# Decoder_relay_4bit_REV_0.net
KiCad netlist of a schematic drawn in EAGLE
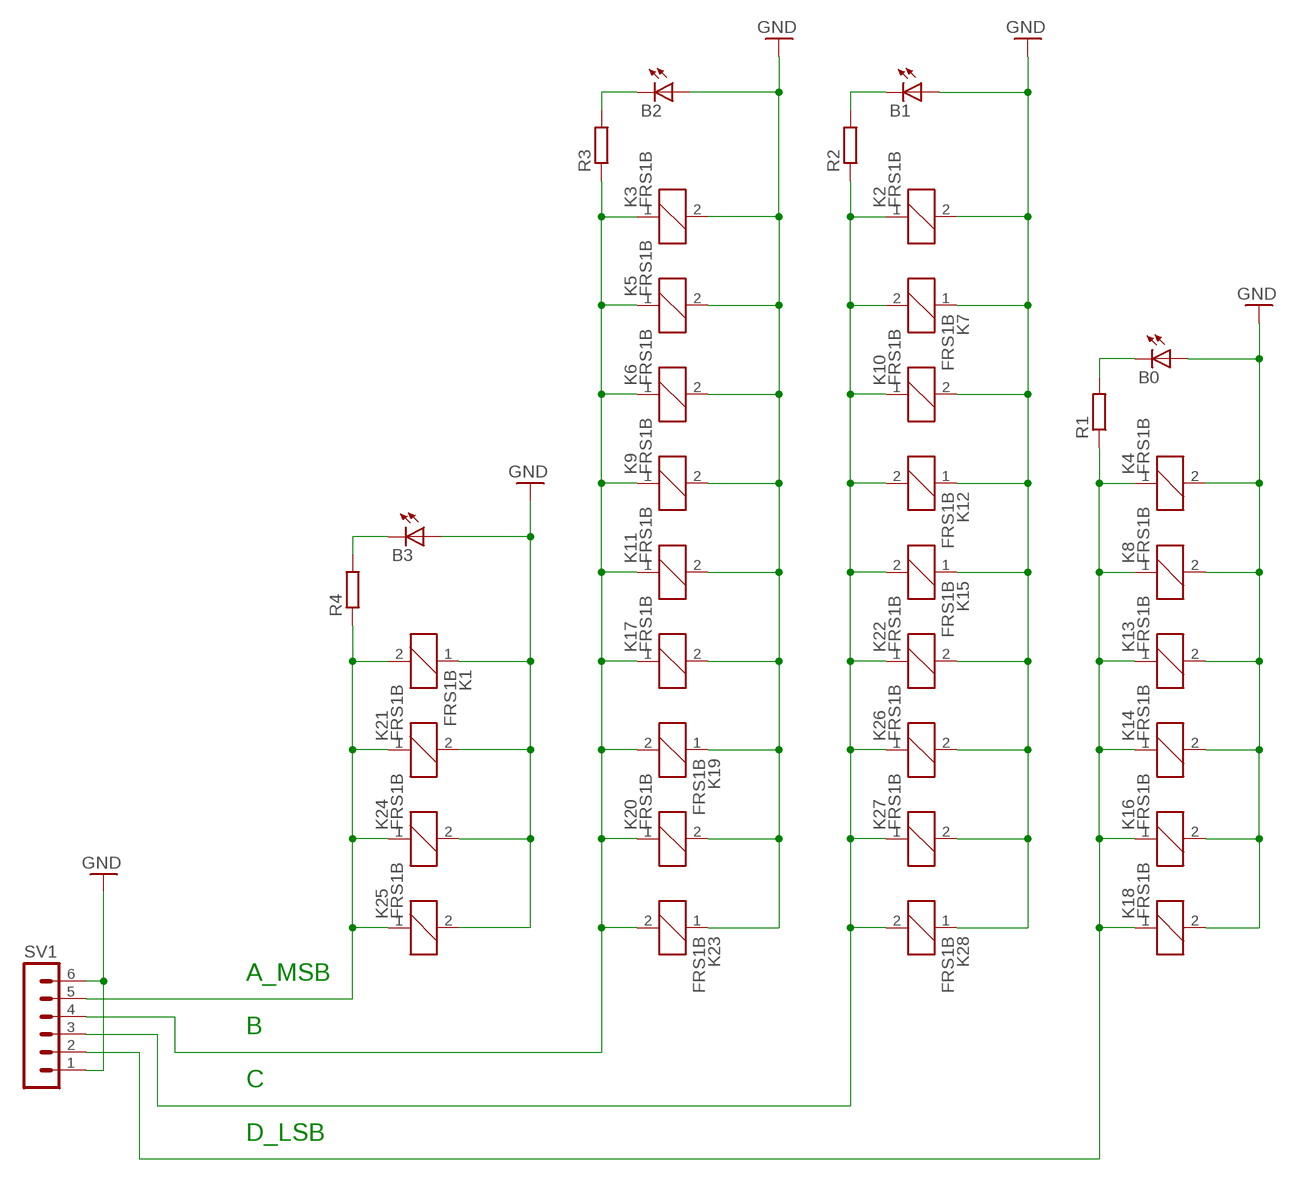
[diagram p0: schematic, sheet 1, part 1 of 2]
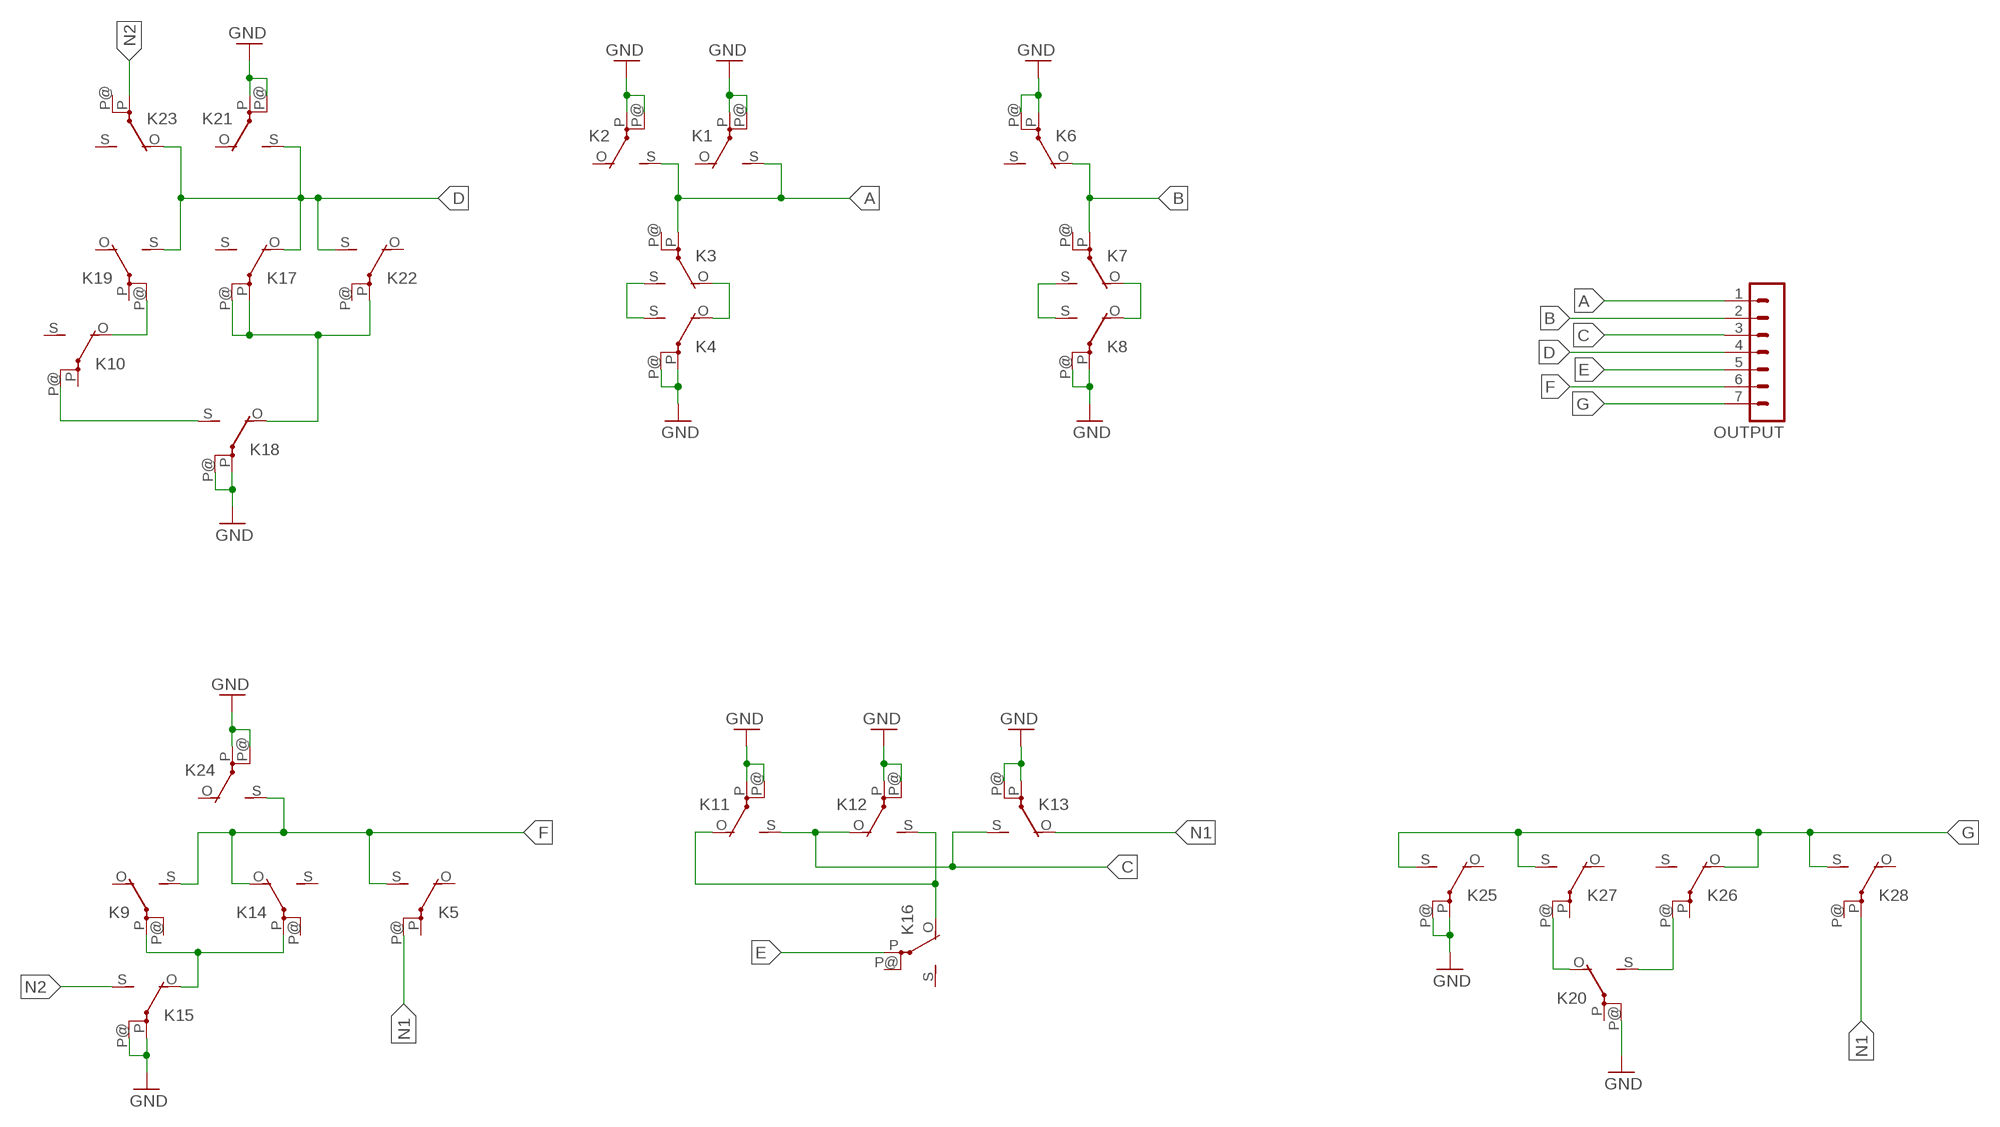
[diagram p1: schematic, sheet 1, part 2 of 2]

(export (version "E")
  (design (tool "Eeschema 10.0.6"))
  (components
    (comp (ref "B0")
      (value "LED3MM")
      (footprint "eagle-import:LED3MM")
      (libsource (lib "eagle-import") (part "LED3MM"))
    )
    (comp (ref "B1")
      (value "LED3MM")
      (footprint "eagle-import:LED3MM")
      (libsource (lib "eagle-import") (part "LED3MM"))
    )
    (comp (ref "B2")
      (value "LED3MM")
      (footprint "eagle-import:LED3MM")
      (libsource (lib "eagle-import") (part "LED3MM"))
    )
    (comp (ref "B3")
      (value "LED3MM")
      (footprint "eagle-import:LED3MM")
      (libsource (lib "eagle-import") (part "LED3MM"))
    )
    (comp (ref "K1")
      (value "FRS1B")
      (footprint "eagle-import:FRS1B")
      (libsource (lib "eagle-import") (part "FRS1B"))
    )
    (comp (ref "K2")
      (value "FRS1B")
      (footprint "eagle-import:FRS1B")
      (libsource (lib "eagle-import") (part "FRS1B"))
    )
    (comp (ref "K3")
      (value "FRS1B")
      (footprint "eagle-import:FRS1B")
      (libsource (lib "eagle-import") (part "FRS1B"))
    )
    (comp (ref "K4")
      (value "FRS1B")
      (footprint "eagle-import:FRS1B")
      (libsource (lib "eagle-import") (part "FRS1B"))
    )
    (comp (ref "K5")
      (value "FRS1B")
      (footprint "eagle-import:FRS1B")
      (libsource (lib "eagle-import") (part "FRS1B"))
    )
    (comp (ref "K6")
      (value "FRS1B")
      (footprint "eagle-import:FRS1B")
      (libsource (lib "eagle-import") (part "FRS1B"))
    )
    (comp (ref "K7")
      (value "FRS1B")
      (footprint "eagle-import:FRS1B")
      (libsource (lib "eagle-import") (part "FRS1B"))
    )
    (comp (ref "K8")
      (value "FRS1B")
      (footprint "eagle-import:FRS1B")
      (libsource (lib "eagle-import") (part "FRS1B"))
    )
    (comp (ref "K9")
      (value "FRS1B")
      (footprint "eagle-import:FRS1B")
      (libsource (lib "eagle-import") (part "FRS1B"))
    )
    (comp (ref "K10")
      (value "FRS1B")
      (footprint "eagle-import:FRS1B")
      (libsource (lib "eagle-import") (part "FRS1B"))
    )
    (comp (ref "K11")
      (value "FRS1B")
      (footprint "eagle-import:FRS1B")
      (libsource (lib "eagle-import") (part "FRS1B"))
    )
    (comp (ref "K12")
      (value "FRS1B")
      (footprint "eagle-import:FRS1B")
      (libsource (lib "eagle-import") (part "FRS1B"))
    )
    (comp (ref "K13")
      (value "FRS1B")
      (footprint "eagle-import:FRS1B")
      (libsource (lib "eagle-import") (part "FRS1B"))
    )
    (comp (ref "K14")
      (value "FRS1B")
      (footprint "eagle-import:FRS1B")
      (libsource (lib "eagle-import") (part "FRS1B"))
    )
    (comp (ref "K15")
      (value "FRS1B")
      (footprint "eagle-import:FRS1B")
      (libsource (lib "eagle-import") (part "FRS1B"))
    )
    (comp (ref "K16")
      (value "FRS1B")
      (footprint "eagle-import:FRS1B")
      (libsource (lib "eagle-import") (part "FRS1B"))
    )
    (comp (ref "K17")
      (value "FRS1B")
      (footprint "eagle-import:FRS1B")
      (libsource (lib "eagle-import") (part "FRS1B"))
    )
    (comp (ref "K18")
      (value "FRS1B")
      (footprint "eagle-import:FRS1B")
      (libsource (lib "eagle-import") (part "FRS1B"))
    )
    (comp (ref "K19")
      (value "FRS1B")
      (footprint "eagle-import:FRS1B")
      (libsource (lib "eagle-import") (part "FRS1B"))
    )
    (comp (ref "K20")
      (value "FRS1B")
      (footprint "eagle-import:FRS1B")
      (libsource (lib "eagle-import") (part "FRS1B"))
    )
    (comp (ref "K21")
      (value "FRS1B")
      (footprint "eagle-import:FRS1B")
      (libsource (lib "eagle-import") (part "FRS1B"))
    )
    (comp (ref "K22")
      (value "FRS1B")
      (footprint "eagle-import:FRS1B")
      (libsource (lib "eagle-import") (part "FRS1B"))
    )
    (comp (ref "K23")
      (value "FRS1B")
      (footprint "eagle-import:FRS1B")
      (libsource (lib "eagle-import") (part "FRS1B"))
    )
    (comp (ref "K24")
      (value "FRS1B")
      (footprint "eagle-import:FRS1B")
      (libsource (lib "eagle-import") (part "FRS1B"))
    )
    (comp (ref "K25")
      (value "FRS1B")
      (footprint "eagle-import:FRS1B")
      (libsource (lib "eagle-import") (part "FRS1B"))
    )
    (comp (ref "K26")
      (value "FRS1B")
      (footprint "eagle-import:FRS1B")
      (libsource (lib "eagle-import") (part "FRS1B"))
    )
    (comp (ref "K27")
      (value "FRS1B")
      (footprint "eagle-import:FRS1B")
      (libsource (lib "eagle-import") (part "FRS1B"))
    )
    (comp (ref "K28")
      (value "FRS1B")
      (footprint "eagle-import:FRS1B")
      (libsource (lib "eagle-import") (part "FRS1B"))
    )
    (comp (ref "OUTPUT")
      (value "MA07-1")
      (footprint "eagle-import:MA07-1")
      (libsource (lib "eagle-import") (part "MA07-1"))
    )
    (comp (ref "R1")
      (value "R-EU_M1206")
      (footprint "eagle-import:M1206")
      (libsource (lib "eagle-import") (part "R-EU_M1206"))
    )
    (comp (ref "R2")
      (value "R-EU_M1206")
      (footprint "eagle-import:M1206")
      (libsource (lib "eagle-import") (part "R-EU_M1206"))
    )
    (comp (ref "R3")
      (value "R-EU_M1206")
      (footprint "eagle-import:M1206")
      (libsource (lib "eagle-import") (part "R-EU_M1206"))
    )
    (comp (ref "R4")
      (value "R-EU_M1206")
      (footprint "eagle-import:M1206")
      (libsource (lib "eagle-import") (part "R-EU_M1206"))
    )
    (comp (ref "SV1")
      (value "MA06-1")
      (footprint "eagle-import:MA06-1")
      (libsource (lib "eagle-import") (part "MA06-1"))
    )
  )
  (nets
    (net (code "1") (name "A") (class "Default")
      (node (ref "K1") (pin "S") (pinfunction "S_S") (pintype "passive"))
      (node (ref "K2") (pin "S") (pinfunction "S_S") (pintype "passive"))
      (node (ref "K3") (pin "P") (pinfunction "P_P") (pintype "passive"))
      (node (ref "OUTPUT") (pin "1") (pinfunction "1_1") (pintype "passive"))
    )
    (net (code "2") (name "B") (class "Default")
      (node (ref "K6") (pin "O") (pinfunction "O_O") (pintype "passive"))
      (node (ref "K7") (pin "P") (pinfunction "P_P") (pintype "passive"))
      (node (ref "OUTPUT") (pin "2") (pinfunction "2_2") (pintype "passive"))
    )
    (net (code "3") (name "C") (class "Default")
      (node (ref "K11") (pin "S") (pinfunction "S_S") (pintype "passive"))
      (node (ref "K12") (pin "O") (pinfunction "O_O") (pintype "passive"))
      (node (ref "K13") (pin "S") (pinfunction "S_S") (pintype "passive"))
      (node (ref "OUTPUT") (pin "3") (pinfunction "3_3") (pintype "passive"))
    )
    (net (code "4") (name "D") (class "Default")
      (node (ref "K17") (pin "O") (pinfunction "O_O") (pintype "passive"))
      (node (ref "K19") (pin "S") (pinfunction "S_S") (pintype "passive"))
      (node (ref "K21") (pin "S") (pinfunction "S_S") (pintype "passive"))
      (node (ref "K22") (pin "S") (pinfunction "S_S") (pintype "passive"))
      (node (ref "K23") (pin "O") (pinfunction "O_O") (pintype "passive"))
      (node (ref "OUTPUT") (pin "4") (pinfunction "4_4") (pintype "passive"))
    )
    (net (code "5") (name "E") (class "Default")
      (node (ref "K16") (pin "P") (pinfunction "P_P") (pintype "passive"))
      (node (ref "OUTPUT") (pin "5") (pinfunction "5_5") (pintype "passive"))
    )
    (net (code "6") (name "F") (class "Default")
      (node (ref "K14") (pin "O") (pinfunction "O_O") (pintype "passive"))
      (node (ref "K24") (pin "S") (pinfunction "S_S") (pintype "passive"))
      (node (ref "K5") (pin "S") (pinfunction "S_S") (pintype "passive"))
      (node (ref "K9") (pin "S") (pinfunction "S_S") (pintype "passive"))
      (node (ref "OUTPUT") (pin "6") (pinfunction "6_6") (pintype "passive"))
    )
    (net (code "7") (name "G") (class "Default")
      (node (ref "K25") (pin "S") (pinfunction "S_S") (pintype "passive"))
      (node (ref "K26") (pin "O") (pinfunction "O_O") (pintype "passive"))
      (node (ref "K27") (pin "S") (pinfunction "S_S") (pintype "passive"))
      (node (ref "K28") (pin "S") (pinfunction "S_S") (pintype "passive"))
      (node (ref "OUTPUT") (pin "7") (pinfunction "7_7") (pintype "passive"))
    )
    (net (code "8") (name "GND") (class "Default")
      (node (ref "B0") (pin "A") (pinfunction "A_A") (pintype "passive"))
      (node (ref "B1") (pin "A") (pinfunction "A_A") (pintype "passive"))
      (node (ref "B2") (pin "A") (pinfunction "A_A") (pintype "passive"))
      (node (ref "B3") (pin "A") (pinfunction "A_A") (pintype "passive"))
      (node (ref "K1") (pin "1") (pinfunction "1_1") (pintype "passive"))
      (node (ref "K1") (pin "P") (pinfunction "P_P") (pintype "passive"))
      (node (ref "K1") (pin "P@") (pinfunction "P_P@") (pintype "passive"))
      (node (ref "K10") (pin "2") (pinfunction "2_2") (pintype "passive"))
      (node (ref "K11") (pin "2") (pinfunction "2_2") (pintype "passive"))
      (node (ref "K11") (pin "P") (pinfunction "P_P") (pintype "passive"))
      (node (ref "K11") (pin "P@") (pinfunction "P_P@") (pintype "passive"))
      (node (ref "K12") (pin "1") (pinfunction "1_1") (pintype "passive"))
      (node (ref "K12") (pin "P") (pinfunction "P_P") (pintype "passive"))
      (node (ref "K12") (pin "P@") (pinfunction "P_P@") (pintype "passive"))
      (node (ref "K13") (pin "2") (pinfunction "2_2") (pintype "passive"))
      (node (ref "K13") (pin "P") (pinfunction "P_P") (pintype "passive"))
      (node (ref "K13") (pin "P@") (pinfunction "P_P@") (pintype "passive"))
      (node (ref "K14") (pin "2") (pinfunction "2_2") (pintype "passive"))
      (node (ref "K15") (pin "1") (pinfunction "1_1") (pintype "passive"))
      (node (ref "K15") (pin "P") (pinfunction "P_P") (pintype "passive"))
      (node (ref "K15") (pin "P@") (pinfunction "P_P@") (pintype "passive"))
      (node (ref "K16") (pin "2") (pinfunction "2_2") (pintype "passive"))
      (node (ref "K17") (pin "2") (pinfunction "2_2") (pintype "passive"))
      (node (ref "K18") (pin "2") (pinfunction "2_2") (pintype "passive"))
      (node (ref "K18") (pin "P") (pinfunction "P_P") (pintype "passive"))
      (node (ref "K18") (pin "P@") (pinfunction "P_P@") (pintype "passive"))
      (node (ref "K19") (pin "1") (pinfunction "1_1") (pintype "passive"))
      (node (ref "K2") (pin "2") (pinfunction "2_2") (pintype "passive"))
      (node (ref "K2") (pin "P") (pinfunction "P_P") (pintype "passive"))
      (node (ref "K2") (pin "P@") (pinfunction "P_P@") (pintype "passive"))
      (node (ref "K20") (pin "2") (pinfunction "2_2") (pintype "passive"))
      (node (ref "K20") (pin "P@") (pinfunction "P_P@") (pintype "passive"))
      (node (ref "K21") (pin "2") (pinfunction "2_2") (pintype "passive"))
      (node (ref "K21") (pin "P") (pinfunction "P_P") (pintype "passive"))
      (node (ref "K21") (pin "P@") (pinfunction "P_P@") (pintype "passive"))
      (node (ref "K22") (pin "2") (pinfunction "2_2") (pintype "passive"))
      (node (ref "K23") (pin "1") (pinfunction "1_1") (pintype "passive"))
      (node (ref "K24") (pin "2") (pinfunction "2_2") (pintype "passive"))
      (node (ref "K24") (pin "P") (pinfunction "P_P") (pintype "passive"))
      (node (ref "K24") (pin "P@") (pinfunction "P_P@") (pintype "passive"))
      (node (ref "K25") (pin "2") (pinfunction "2_2") (pintype "passive"))
      (node (ref "K25") (pin "P") (pinfunction "P_P") (pintype "passive"))
      (node (ref "K25") (pin "P@") (pinfunction "P_P@") (pintype "passive"))
      (node (ref "K26") (pin "2") (pinfunction "2_2") (pintype "passive"))
      (node (ref "K27") (pin "2") (pinfunction "2_2") (pintype "passive"))
      (node (ref "K28") (pin "1") (pinfunction "1_1") (pintype "passive"))
      (node (ref "K3") (pin "2") (pinfunction "2_2") (pintype "passive"))
      (node (ref "K4") (pin "2") (pinfunction "2_2") (pintype "passive"))
      (node (ref "K4") (pin "P") (pinfunction "P_P") (pintype "passive"))
      (node (ref "K4") (pin "P@") (pinfunction "P_P@") (pintype "passive"))
      (node (ref "K5") (pin "2") (pinfunction "2_2") (pintype "passive"))
      (node (ref "K6") (pin "2") (pinfunction "2_2") (pintype "passive"))
      (node (ref "K6") (pin "P") (pinfunction "P_P") (pintype "passive"))
      (node (ref "K6") (pin "P@") (pinfunction "P_P@") (pintype "passive"))
      (node (ref "K7") (pin "1") (pinfunction "1_1") (pintype "passive"))
      (node (ref "K8") (pin "2") (pinfunction "2_2") (pintype "passive"))
      (node (ref "K8") (pin "P") (pinfunction "P_P") (pintype "passive"))
      (node (ref "K8") (pin "P@") (pinfunction "P_P@") (pintype "passive"))
      (node (ref "K9") (pin "2") (pinfunction "2_2") (pintype "passive"))
      (node (ref "SV1") (pin "1") (pinfunction "1_1") (pintype "passive"))
      (node (ref "SV1") (pin "6") (pinfunction "6_6") (pintype "passive"))
    )
    (net (code "9") (name "N1") (class "Default")
      (node (ref "K13") (pin "O") (pinfunction "O_O") (pintype "passive"))
      (node (ref "K28") (pin "P") (pinfunction "P_P") (pintype "passive"))
      (node (ref "K5") (pin "P@") (pinfunction "P_P@") (pintype "passive"))
    )
    (net (code "10") (name "N2") (class "Default")
      (node (ref "K15") (pin "S") (pinfunction "S_S") (pintype "passive"))
      (node (ref "K23") (pin "P") (pinfunction "P_P") (pintype "passive"))
    )
    (net (code "11") (name "Net-(B0-C)") (class "Default")
      (node (ref "B0") (pin "K") (pinfunction "C_K") (pintype "passive"))
      (node (ref "R1") (pin "2") (pinfunction "2_2") (pintype "passive"))
    )
    (net (code "12") (name "Net-(B1-C)") (class "Default")
      (node (ref "B1") (pin "K") (pinfunction "C_K") (pintype "passive"))
      (node (ref "R2") (pin "2") (pinfunction "2_2") (pintype "passive"))
    )
    (net (code "13") (name "Net-(B2-C)") (class "Default")
      (node (ref "B2") (pin "K") (pinfunction "C_K") (pintype "passive"))
      (node (ref "R3") (pin "2") (pinfunction "2_2") (pintype "passive"))
    )
    (net (code "14") (name "Net-(B3-C)") (class "Default")
      (node (ref "B3") (pin "K") (pinfunction "C_K") (pintype "passive"))
      (node (ref "R4") (pin "2") (pinfunction "2_2") (pintype "passive"))
    )
    (net (code "15") (name "Net-(K1-Pad2)") (class "Default")
      (node (ref "K1") (pin "2") (pinfunction "2_2") (pintype "passive"))
      (node (ref "K21") (pin "1") (pinfunction "1_1") (pintype "passive"))
      (node (ref "K24") (pin "1") (pinfunction "1_1") (pintype "passive"))
      (node (ref "K25") (pin "1") (pinfunction "1_1") (pintype "passive"))
      (node (ref "R4") (pin "1") (pinfunction "1_1") (pintype "passive"))
      (node (ref "SV1") (pin "5") (pinfunction "5_5") (pintype "passive"))
    )
    (net (code "16") (name "Net-(K3-PadO)") (class "Default")
      (node (ref "K3") (pin "O") (pinfunction "O_O") (pintype "passive"))
      (node (ref "K4") (pin "O") (pinfunction "O_O") (pintype "passive"))
    )
    (net (code "17") (name "Net-(K3-PadS)") (class "Default")
      (node (ref "K3") (pin "S") (pinfunction "S_S") (pintype "passive"))
      (node (ref "K4") (pin "S") (pinfunction "S_S") (pintype "passive"))
    )
    (net (code "18") (name "Net-(K7-PadO)") (class "Default")
      (node (ref "K7") (pin "O") (pinfunction "O_O") (pintype "passive"))
      (node (ref "K8") (pin "O") (pinfunction "O_O") (pintype "passive"))
    )
    (net (code "19") (name "Net-(K7-PadS)") (class "Default")
      (node (ref "K7") (pin "S") (pinfunction "S_S") (pintype "passive"))
      (node (ref "K8") (pin "S") (pinfunction "S_S") (pintype "passive"))
    )
    (net (code "20") (name "Net-(K10-Pad1)") (class "Default")
      (node (ref "K10") (pin "1") (pinfunction "1_1") (pintype "passive"))
      (node (ref "K12") (pin "2") (pinfunction "2_2") (pintype "passive"))
      (node (ref "K15") (pin "2") (pinfunction "2_2") (pintype "passive"))
      (node (ref "K2") (pin "1") (pinfunction "1_1") (pintype "passive"))
      (node (ref "K22") (pin "1") (pinfunction "1_1") (pintype "passive"))
      (node (ref "K26") (pin "1") (pinfunction "1_1") (pintype "passive"))
      (node (ref "K27") (pin "1") (pinfunction "1_1") (pintype "passive"))
      (node (ref "K28") (pin "2") (pinfunction "2_2") (pintype "passive"))
      (node (ref "K7") (pin "2") (pinfunction "2_2") (pintype "passive"))
      (node (ref "R2") (pin "1") (pinfunction "1_1") (pintype "passive"))
      (node (ref "SV1") (pin "3") (pinfunction "3_3") (pintype "passive"))
    )
    (net (code "21") (name "Net-(K10-PadO)") (class "Default")
      (node (ref "K10") (pin "O") (pinfunction "O_O") (pintype "passive"))
      (node (ref "K19") (pin "P@") (pinfunction "P_P@") (pintype "passive"))
    )
    (net (code "22") (name "Net-(K10B-P-PadP@)") (class "Default")
      (node (ref "K10") (pin "P@") (pinfunction "P_P@") (pintype "passive"))
      (node (ref "K18") (pin "S") (pinfunction "S_S") (pintype "passive"))
    )
    (net (code "23") (name "Net-(K11-Pad1)") (class "Default")
      (node (ref "K11") (pin "1") (pinfunction "1_1") (pintype "passive"))
      (node (ref "K17") (pin "1") (pinfunction "1_1") (pintype "passive"))
      (node (ref "K19") (pin "2") (pinfunction "2_2") (pintype "passive"))
      (node (ref "K20") (pin "1") (pinfunction "1_1") (pintype "passive"))
      (node (ref "K23") (pin "2") (pinfunction "2_2") (pintype "passive"))
      (node (ref "K3") (pin "1") (pinfunction "1_1") (pintype "passive"))
      (node (ref "K5") (pin "1") (pinfunction "1_1") (pintype "passive"))
      (node (ref "K6") (pin "1") (pinfunction "1_1") (pintype "passive"))
      (node (ref "K9") (pin "1") (pinfunction "1_1") (pintype "passive"))
      (node (ref "R3") (pin "1") (pinfunction "1_1") (pintype "passive"))
      (node (ref "SV1") (pin "4") (pinfunction "4_4") (pintype "passive"))
    )
    (net (code "24") (name "Net-(K11-PadO)") (class "Default")
      (node (ref "K11") (pin "O") (pinfunction "O_O") (pintype "passive"))
      (node (ref "K12") (pin "S") (pinfunction "S_S") (pintype "passive"))
      (node (ref "K16") (pin "O") (pinfunction "O_O") (pintype "passive"))
    )
    (net (code "25") (name "Net-(K13-Pad1)") (class "Default")
      (node (ref "K13") (pin "1") (pinfunction "1_1") (pintype "passive"))
      (node (ref "K14") (pin "1") (pinfunction "1_1") (pintype "passive"))
      (node (ref "K16") (pin "1") (pinfunction "1_1") (pintype "passive"))
      (node (ref "K18") (pin "1") (pinfunction "1_1") (pintype "passive"))
      (node (ref "K4") (pin "1") (pinfunction "1_1") (pintype "passive"))
      (node (ref "K8") (pin "1") (pinfunction "1_1") (pintype "passive"))
      (node (ref "R1") (pin "1") (pinfunction "1_1") (pintype "passive"))
      (node (ref "SV1") (pin "2") (pinfunction "2_2") (pintype "passive"))
    )
    (net (code "26") (name "Net-(K14-PadP)") (class "Default")
      (node (ref "K14") (pin "P") (pinfunction "P_P") (pintype "passive"))
      (node (ref "K15") (pin "O") (pinfunction "O_O") (pintype "passive"))
      (node (ref "K9") (pin "P") (pinfunction "P_P") (pintype "passive"))
    )
    (net (code "27") (name "Net-(K17-PadP)") (class "Default")
      (node (ref "K17") (pin "P") (pinfunction "P_P") (pintype "passive"))
      (node (ref "K17") (pin "P@") (pinfunction "P_P@") (pintype "passive"))
      (node (ref "K18") (pin "O") (pinfunction "O_O") (pintype "passive"))
      (node (ref "K22") (pin "P") (pinfunction "P_P") (pintype "passive"))
    )
    (net (code "28") (name "Net-(K20-PadO)") (class "Default")
      (node (ref "K20") (pin "O") (pinfunction "O_O") (pintype "passive"))
      (node (ref "K27") (pin "P@") (pinfunction "P_P@") (pintype "passive"))
    )
    (net (code "29") (name "Net-(K20-PadS)") (class "Default")
      (node (ref "K20") (pin "S") (pinfunction "S_S") (pintype "passive"))
      (node (ref "K26") (pin "P@") (pinfunction "P_P@") (pintype "passive"))
    )
    (net (code "30") (name "unconnected-(K1-PadO)") (class "Default")
      (node (ref "K1") (pin "O") (pinfunction "O_O") (pintype "passive"))
    )
    (net (code "31") (name "unconnected-(K2-PadO)") (class "Default")
      (node (ref "K2") (pin "O") (pinfunction "O_O") (pintype "passive"))
    )
    (net (code "32") (name "unconnected-(K3B-P-PadP@)") (class "Default")
      (node (ref "K3") (pin "P@") (pinfunction "P_P@") (pintype "passive"))
    )
    (net (code "33") (name "unconnected-(K5-PadO)") (class "Default")
      (node (ref "K5") (pin "O") (pinfunction "O_O") (pintype "passive"))
    )
    (net (code "34") (name "unconnected-(K5-PadP)") (class "Default")
      (node (ref "K5") (pin "P") (pinfunction "P_P") (pintype "passive"))
    )
    (net (code "35") (name "unconnected-(K6-PadS)") (class "Default")
      (node (ref "K6") (pin "S") (pinfunction "S_S") (pintype "passive"))
    )
    (net (code "36") (name "unconnected-(K7B-P-PadP@)") (class "Default")
      (node (ref "K7") (pin "P@") (pinfunction "P_P@") (pintype "passive"))
    )
    (net (code "37") (name "unconnected-(K9-PadO)") (class "Default")
      (node (ref "K9") (pin "O") (pinfunction "O_O") (pintype "passive"))
    )
    (net (code "38") (name "unconnected-(K9B-P-PadP@)") (class "Default")
      (node (ref "K9") (pin "P@") (pinfunction "P_P@") (pintype "passive"))
    )
    (net (code "39") (name "unconnected-(K10-PadP)") (class "Default")
      (node (ref "K10") (pin "P") (pinfunction "P_P") (pintype "passive"))
    )
    (net (code "40") (name "unconnected-(K10-PadS)") (class "Default")
      (node (ref "K10") (pin "S") (pinfunction "S_S") (pintype "passive"))
    )
    (net (code "41") (name "unconnected-(K14-PadS)") (class "Default")
      (node (ref "K14") (pin "S") (pinfunction "S_S") (pintype "passive"))
    )
    (net (code "42") (name "unconnected-(K14B-P-PadP@)") (class "Default")
      (node (ref "K14") (pin "P@") (pinfunction "P_P@") (pintype "passive"))
    )
    (net (code "43") (name "unconnected-(K16-PadS)") (class "Default")
      (node (ref "K16") (pin "S") (pinfunction "S_S") (pintype "passive"))
    )
    (net (code "44") (name "unconnected-(K16B-P-PadP@)") (class "Default")
      (node (ref "K16") (pin "P@") (pinfunction "P_P@") (pintype "passive"))
    )
    (net (code "45") (name "unconnected-(K17-PadS)") (class "Default")
      (node (ref "K17") (pin "S") (pinfunction "S_S") (pintype "passive"))
    )
    (net (code "46") (name "unconnected-(K19-PadO)") (class "Default")
      (node (ref "K19") (pin "O") (pinfunction "O_O") (pintype "passive"))
    )
    (net (code "47") (name "unconnected-(K19-PadP)") (class "Default")
      (node (ref "K19") (pin "P") (pinfunction "P_P") (pintype "passive"))
    )
    (net (code "48") (name "unconnected-(K20-PadP)") (class "Default")
      (node (ref "K20") (pin "P") (pinfunction "P_P") (pintype "passive"))
    )
    (net (code "49") (name "unconnected-(K21-PadO)") (class "Default")
      (node (ref "K21") (pin "O") (pinfunction "O_O") (pintype "passive"))
    )
    (net (code "50") (name "unconnected-(K22-PadO)") (class "Default")
      (node (ref "K22") (pin "O") (pinfunction "O_O") (pintype "passive"))
    )
    (net (code "51") (name "unconnected-(K22B-P-PadP@)") (class "Default")
      (node (ref "K22") (pin "P@") (pinfunction "P_P@") (pintype "passive"))
    )
    (net (code "52") (name "unconnected-(K23-PadS)") (class "Default")
      (node (ref "K23") (pin "S") (pinfunction "S_S") (pintype "passive"))
    )
    (net (code "53") (name "unconnected-(K23B-P-PadP@)") (class "Default")
      (node (ref "K23") (pin "P@") (pinfunction "P_P@") (pintype "passive"))
    )
    (net (code "54") (name "unconnected-(K24-PadO)") (class "Default")
      (node (ref "K24") (pin "O") (pinfunction "O_O") (pintype "passive"))
    )
    (net (code "55") (name "unconnected-(K25-PadO)") (class "Default")
      (node (ref "K25") (pin "O") (pinfunction "O_O") (pintype "passive"))
    )
    (net (code "56") (name "unconnected-(K26-PadP)") (class "Default")
      (node (ref "K26") (pin "P") (pinfunction "P_P") (pintype "passive"))
    )
    (net (code "57") (name "unconnected-(K26-PadS)") (class "Default")
      (node (ref "K26") (pin "S") (pinfunction "S_S") (pintype "passive"))
    )
    (net (code "58") (name "unconnected-(K27-PadO)") (class "Default")
      (node (ref "K27") (pin "O") (pinfunction "O_O") (pintype "passive"))
    )
    (net (code "59") (name "unconnected-(K27-PadP)") (class "Default")
      (node (ref "K27") (pin "P") (pinfunction "P_P") (pintype "passive"))
    )
    (net (code "60") (name "unconnected-(K28-PadO)") (class "Default")
      (node (ref "K28") (pin "O") (pinfunction "O_O") (pintype "passive"))
    )
    (net (code "61") (name "unconnected-(K28B-P-PadP@)") (class "Default")
      (node (ref "K28") (pin "P@") (pinfunction "P_P@") (pintype "passive"))
    )
  )
)
